# Fri3D_2026_Power.net
KiCad netlist of a schematic drawn in Altium Designer
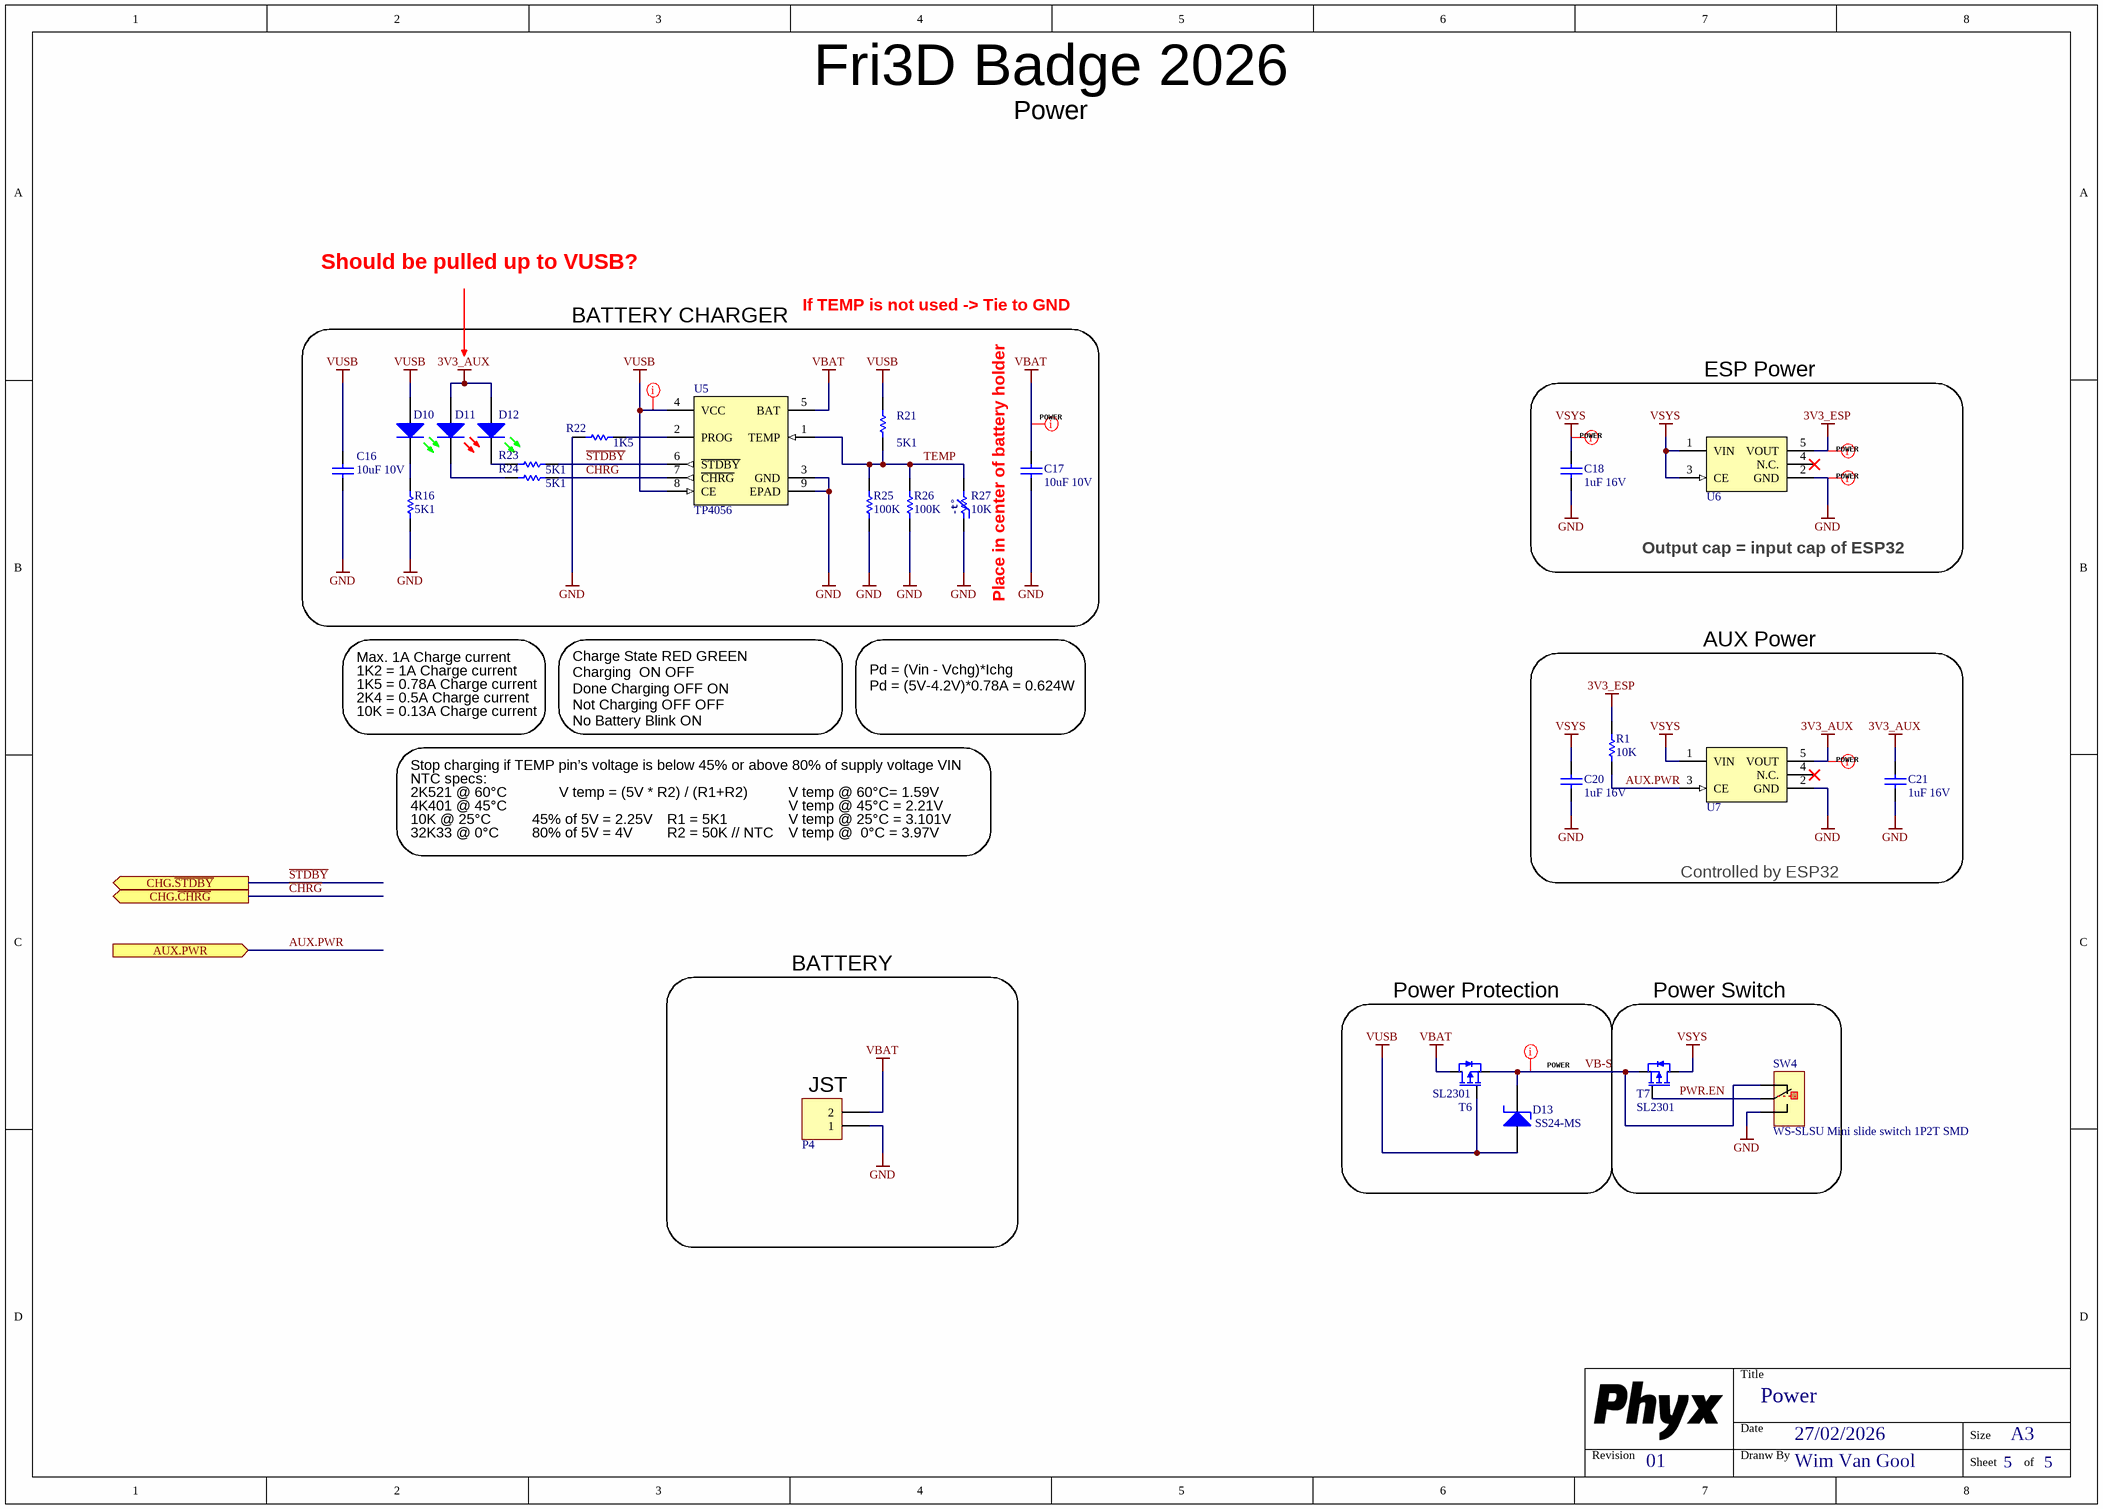
[diagram p0: Fri3D_2026_Power.SchDoc]

(export (version "E")
  (design (tool "Eeschema 10.0.6"))
  (components
    (comp (ref "C16")
      (value "10uF 10V")
      (footprint "C0805_N")
      (description "Capacitor Ceramic")
      (libsource (lib "Phyx_Components") (part "CAP_CERAMIC"))
    )
    (comp (ref "C17")
      (value "10uF 10V")
      (footprint "C0805_N")
      (description "Capacitor Ceramic")
      (libsource (lib "Phyx_Components") (part "CAP_CERAMIC"))
    )
    (comp (ref "C18")
      (value "1uF 16V")
      (footprint "C0603_N")
      (description "Capacitor Ceramic")
      (libsource (lib "Phyx_Components") (part "CAP_CERAMIC"))
    )
    (comp (ref "C20")
      (value "1uF 16V")
      (footprint "C0603_N")
      (description "Capacitor Ceramic")
      (libsource (lib "Phyx_Components") (part "CAP_CERAMIC"))
    )
    (comp (ref "C21")
      (value "1uF 16V")
      (footprint "C0603_N")
      (description "Capacitor Ceramic")
      (libsource (lib "Phyx_Components") (part "CAP_CERAMIC"))
    )
    (comp (ref "D10")
      (value "Default 0805 Green LED")
      (footprint "LED_0805_GR")
      (description "=Description")
      (libsource (lib "Phyx_Components") (part "LED_GREEN"))
    )
    (comp (ref "D11")
      (value "Default 0805 Red LED")
      (footprint "LED_0805_RD")
      (description "=Description")
      (libsource (lib "Phyx_Components") (part "LED_RED"))
    )
    (comp (ref "D12")
      (value "Default 0805 Green LED")
      (footprint "LED_0805_GR")
      (description "=Description")
      (libsource (lib "Phyx_Components") (part "LED_GREEN"))
    )
    (comp (ref "D13")
      (value "SS24-MS")
      (footprint "DO-214AC_AC")
      (description "=Description")
      (fields (field (name "Comment") "40V 2A 550mV@2A DO-214 Schottky"))
      (libsource (lib "Phyx_Components") (part "Schottky_AC"))
    )
    (comp (ref "P4")
      (value "Header RA 1.5mm Shrouded S2B-ZR-SM4A-TF")
      (footprint "JST_ZH_S2B-ZR-SM4A-TF")
      (libsource (lib "Phyx_Components") (part "Header 2"))
    )
    (comp (ref "R1")
      (value "10K")
      (footprint "R0603_N")
      (libsource (lib "Phyx_Components") (part "RESISTOR"))
    )
    (comp (ref "R16")
      (value "5K1")
      (footprint "R0603_N")
      (libsource (lib "Phyx_Components") (part "RESISTOR"))
    )
    (comp (ref "R21")
      (value "5K1")
      (footprint "R0603_N")
      (libsource (lib "Phyx_Components") (part "RESISTOR"))
    )
    (comp (ref "R22")
      (value "1K5")
      (footprint "R0603_N")
      (libsource (lib "Phyx_Components") (part "RESISTOR"))
    )
    (comp (ref "R23")
      (value "5K1")
      (footprint "R0603_N")
      (libsource (lib "Phyx_Components") (part "RESISTOR"))
    )
    (comp (ref "R24")
      (value "5K1")
      (footprint "R0603_N")
      (libsource (lib "Phyx_Components") (part "RESISTOR"))
    )
    (comp (ref "R25")
      (value "100K")
      (footprint "R0603_N")
      (libsource (lib "Phyx_Components") (part "RESISTOR"))
    )
    (comp (ref "R26")
      (value "100K")
      (footprint "R0603_N")
      (libsource (lib "Phyx_Components") (part "RESISTOR"))
    )
    (comp (ref "R27")
      (value "10K")
      (footprint "R0402")
      (libsource (lib "Phyx_Components") (part "RESISTOR_NTC"))
    )
    (comp (ref "SW4")
      (value "WS-SLSU Mini slide switch 1P2T SMD")
      (footprint "WE_450404015514")
      (libsource (lib "Phyx_Components") (part "SW_1P2T"))
    )
    (comp (ref "T6")
      (value "SL2301")
      (footprint "SOT23-3")
      (description "=Description")
      (fields (field (name "Comment") "-2.3A -20V P-Ch MOSFET Vgs -1V"))
      (libsource (lib "Phyx_Components") (part "P_MOSFET_GSD"))
    )
    (comp (ref "T7")
      (value "SL2301")
      (footprint "SOT23-3")
      (description "=Description")
      (fields (field (name "Comment") "-2.3A -20V P-Ch MOSFET Vgs -1V"))
      (libsource (lib "Phyx_Components") (part "P_MOSFET_GSD"))
    )
    (comp (ref "U5")
      (value "TP4056")
      (footprint "SOIC_N_8_TH")
      (description "=Description")
      (fields (field (name "Comment") "Single Cell LiIon charger max 1A"))
      (libsource (lib "Phyx_Components") (part "TP4056"))
    )
    (comp (ref "U6")
      (value "3V3 LDO 700mA 50mV")
      (footprint "SOT23-5")
      (description "=Designator")
      (libsource (lib "Phyx_Components") (part "XC6210_SOT"))
    )
    (comp (ref "U7")
      (value "3V3 LDO 700mA 50mV")
      (footprint "SOT23-5")
      (description "=Designator")
      (libsource (lib "Phyx_Components") (part "XC6210_SOT"))
    )
  )
  (nets
    (net (code "1") (name "/AUX.PWR") (class "Default")
      (node (ref "R1") (pin "2") (pinfunction "2_2") (pintype "passive"))
      (node (ref "U7") (pin "3") (pinfunction "CE_3") (pintype "input"))
    )
    (net (code "2") (name "/PWR.EN") (class "Default")
      (node (ref "SW4") (pin "2") (pinfunction "2_2") (pintype "passive"))
      (node (ref "T7") (pin "1") (pinfunction "G_1") (pintype "passive"))
    )
    (net (code "3") (name "/TEMP") (class "Default")
      (node (ref "R21") (pin "2") (pinfunction "2_2") (pintype "passive"))
      (node (ref "R25") (pin "1") (pinfunction "1_1") (pintype "passive"))
      (node (ref "R26") (pin "1") (pinfunction "1_1") (pintype "passive"))
      (node (ref "R27") (pin "1") (pinfunction "1_1") (pintype "passive"))
      (node (ref "U5") (pin "1") (pinfunction "TEMP_1") (pintype "input"))
    )
    (net (code "4") (name "/VB-S") (class "Default")
      (node (ref "D13") (pin "C") (pinfunction "C_C") (pintype "passive"))
      (node (ref "SW4") (pin "1") (pinfunction "1_1") (pintype "passive"))
      (node (ref "T6") (pin "2") (pinfunction "S_2") (pintype "passive"))
      (node (ref "T7") (pin "2") (pinfunction "S_2") (pintype "passive"))
    )
    (net (code "5") (name "/~{CHRG}") (class "Default")
      (node (ref "R24") (pin "2") (pinfunction "2_2") (pintype "passive"))
      (node (ref "U5") (pin "7") (pinfunction "~{CHRG}_7") (pintype "output"))
    )
    (net (code "6") (name "/~{STDBY}") (class "Default")
      (node (ref "R23") (pin "2") (pinfunction "2_2") (pintype "passive"))
      (node (ref "U5") (pin "6") (pinfunction "~{STDBY}_6") (pintype "output"))
    )
    (net (code "7") (name "3V3_AUX") (class "Default")
      (node (ref "C21") (pin "1") (pinfunction "1_1") (pintype "passive"))
      (node (ref "D11") (pin "1") (pinfunction "A_1") (pintype "passive"))
      (node (ref "D12") (pin "1") (pinfunction "A_1") (pintype "passive"))
      (node (ref "U7") (pin "5") (pinfunction "VOUT_5") (pintype "power_in"))
    )
    (net (code "8") (name "3V3_ESP") (class "Default")
      (node (ref "R1") (pin "1") (pinfunction "1_1") (pintype "passive"))
      (node (ref "U6") (pin "5") (pinfunction "VOUT_5") (pintype "power_in"))
    )
    (net (code "9") (name "GND") (class "Default")
      (node (ref "C16") (pin "2") (pinfunction "2_2") (pintype "passive"))
      (node (ref "C17") (pin "2") (pinfunction "2_2") (pintype "passive"))
      (node (ref "C18") (pin "2") (pinfunction "2_2") (pintype "passive"))
      (node (ref "C20") (pin "2") (pinfunction "2_2") (pintype "passive"))
      (node (ref "C21") (pin "2") (pinfunction "2_2") (pintype "passive"))
      (node (ref "P4") (pin "1") (pinfunction "1_1") (pintype "passive"))
      (node (ref "R16") (pin "2") (pinfunction "2_2") (pintype "passive"))
      (node (ref "R22") (pin "2") (pinfunction "2_2") (pintype "passive"))
      (node (ref "R25") (pin "2") (pinfunction "2_2") (pintype "passive"))
      (node (ref "R26") (pin "2") (pinfunction "2_2") (pintype "passive"))
      (node (ref "R27") (pin "2") (pinfunction "2_2") (pintype "passive"))
      (node (ref "SW4") (pin "3") (pinfunction "3_3") (pintype "passive"))
      (node (ref "U5") (pin "3") (pinfunction "GND_3") (pintype "power_in"))
      (node (ref "U5") (pin "9") (pinfunction "EPAD_9") (pintype "power_in"))
      (node (ref "U6") (pin "2") (pinfunction "GND_2") (pintype "power_in"))
      (node (ref "U7") (pin "2") (pinfunction "GND_2") (pintype "power_in"))
    )
    (net (code "10") (name "Net-(D10-K)") (class "Default")
      (node (ref "D10") (pin "2") (pinfunction "K_2") (pintype "passive"))
      (node (ref "R16") (pin "1") (pinfunction "1_1") (pintype "passive"))
    )
    (net (code "11") (name "Net-(D11-K)") (class "Default")
      (node (ref "D11") (pin "2") (pinfunction "K_2") (pintype "passive"))
      (node (ref "R24") (pin "1") (pinfunction "1_1") (pintype "passive"))
    )
    (net (code "12") (name "Net-(D12-K)") (class "Default")
      (node (ref "D12") (pin "2") (pinfunction "K_2") (pintype "passive"))
      (node (ref "R23") (pin "1") (pinfunction "1_1") (pintype "passive"))
    )
    (net (code "13") (name "Net-(U5-PROG)") (class "Default")
      (node (ref "R22") (pin "1") (pinfunction "1_1") (pintype "passive"))
      (node (ref "U5") (pin "2") (pinfunction "PROG_2") (pintype "passive"))
    )
    (net (code "14") (name "VBAT") (class "Default")
      (node (ref "C17") (pin "1") (pinfunction "1_1") (pintype "passive"))
      (node (ref "P4") (pin "2") (pinfunction "2_2") (pintype "passive"))
      (node (ref "T6") (pin "3") (pinfunction "D_3") (pintype "passive"))
      (node (ref "U5") (pin "5") (pinfunction "BAT_5") (pintype "power_in"))
    )
    (net (code "15") (name "VSYS") (class "Default")
      (node (ref "C18") (pin "1") (pinfunction "1_1") (pintype "passive"))
      (node (ref "C20") (pin "1") (pinfunction "1_1") (pintype "passive"))
      (node (ref "T7") (pin "3") (pinfunction "D_3") (pintype "passive"))
      (node (ref "U6") (pin "1") (pinfunction "VIN_1") (pintype "power_in"))
      (node (ref "U6") (pin "3") (pinfunction "CE_3") (pintype "input"))
      (node (ref "U7") (pin "1") (pinfunction "VIN_1") (pintype "power_in"))
    )
    (net (code "16") (name "VUSB") (class "Default")
      (node (ref "C16") (pin "1") (pinfunction "1_1") (pintype "passive"))
      (node (ref "D10") (pin "1") (pinfunction "A_1") (pintype "passive"))
      (node (ref "D13") (pin "A") (pinfunction "A_A") (pintype "passive"))
      (node (ref "R21") (pin "1") (pinfunction "1_1") (pintype "passive"))
      (node (ref "T6") (pin "1") (pinfunction "G_1") (pintype "passive"))
      (node (ref "U5") (pin "4") (pinfunction "VCC_4") (pintype "power_in"))
      (node (ref "U5") (pin "8") (pinfunction "CE_8") (pintype "input"))
    )
    (net (code "17") (name "unconnected-(U6-N.C.-Pad4)") (class "Default")
      (node (ref "U6") (pin "4") (pinfunction "N.C._4") (pintype "passive+no_connect"))
    )
    (net (code "18") (name "unconnected-(U7-N.C.-Pad4)") (class "Default")
      (node (ref "U7") (pin "4") (pinfunction "N.C._4") (pintype "passive+no_connect"))
    )
  )
)
